# Sheet1.net
KiCad netlist of a schematic drawn in Altium Designer
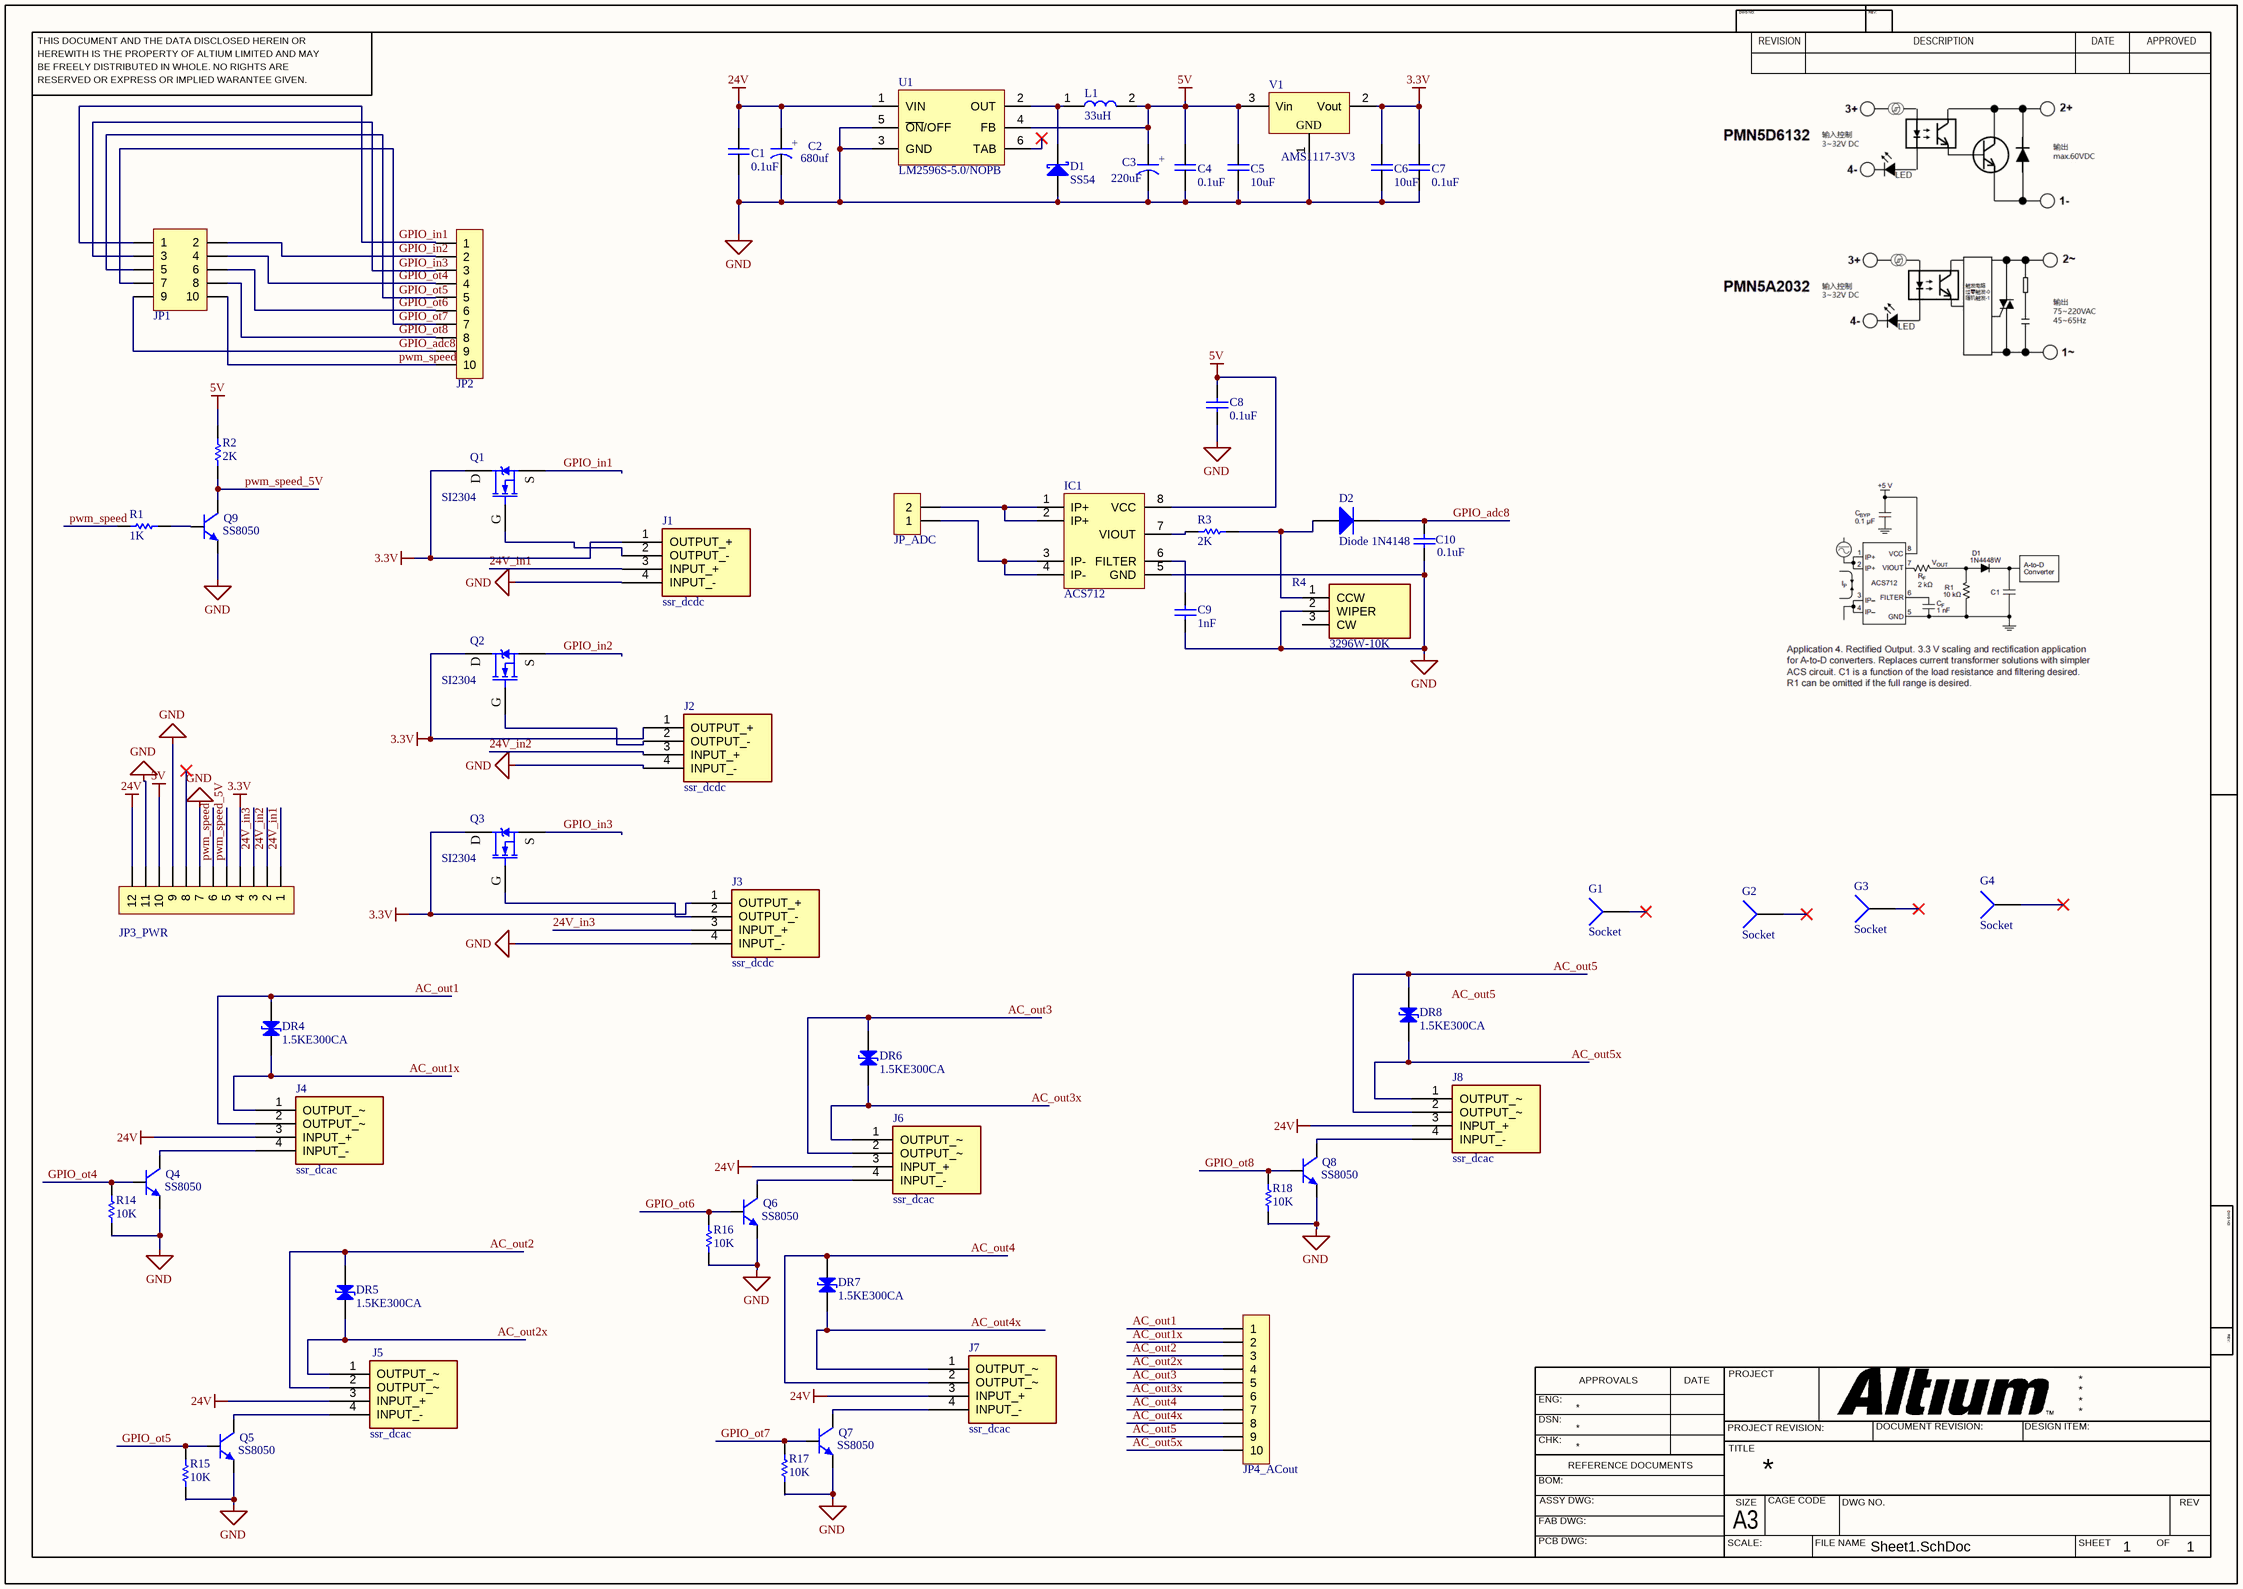
[diagram p0: Sheet1.SchDoc]

(export (version "E")
  (design (tool "Eeschema 10.0.6"))
  (components
    (comp (ref "C1") (value "0.1uF") (footprint "C 0805_M") (libsource (lib "LM2596S_5.0") (part "CAP-SMT")))
    (comp (ref "C2")
      (value "680uf")
      (footprint "CAP 5.0*12.5*20")
      (description "CAP-SMD")
      (libsource (lib "LM2596S_5.0") (part "CAP-SMD"))
    )
    (comp (ref "C3")
      (value "220uF")
      (footprint "CAP 5.0*10*16")
      (description "CAP-SMD")
      (libsource (lib "LM2596S_5.0") (part "CAP-SMD"))
    )
    (comp (ref "C4") (value "0.1uF") (footprint "C 0805_M") (libsource (lib "LM2596S_5.0") (part "CAP-SMT")))
    (comp (ref "C5") (value "10uF") (footprint "C 0805_M") (libsource (lib "LM2596S_5.0") (part "CAP-SMT")))
    (comp (ref "C6") (value "10uF") (footprint "C 0805_M") (libsource (lib "LM2596S_5.0") (part "CAP-SMT")))
    (comp (ref "C7") (value "0.1uF") (footprint "C 0805_M") (libsource (lib "LM2596S_5.0") (part "CAP-SMT")))
    (comp (ref "C8")
      (value "0.1uF")
      (footprint "C 0805_M")
      (description "Capacitor")
      (fields (field (name "PUBLISHER") "Altium Limited"))
      (libsource (lib "Miscellaneous Devices") (part "Cap"))
    )
    (comp (ref "C9")
      (value "1nF")
      (footprint "C 0805_M")
      (description "Capacitor")
      (fields (field (name "PUBLISHER") "Altium Limited"))
      (libsource (lib "Miscellaneous Devices") (part "Cap"))
    )
    (comp (ref "C10")
      (value "0.1uF")
      (footprint "C 0805_M")
      (description "Capacitor")
      (fields (field (name "PUBLISHER") "Altium Limited"))
      (libsource (lib "Miscellaneous Devices") (part "Cap"))
    )
    (comp (ref "D1") (value "SS54") (footprint "SMC") (libsource (lib "LM2596S_5.0") (part "DIO")))
    (comp (ref "D2")
      (value "Diode 1N4148")
      (footprint "SOD-123")
      (description "High Conductance Fast Diode")
      (fields (field (name "PUBLISHER") "Altium Limited"))
      (libsource (lib "Miscellaneous Devices") (part "Diode 1N4148"))
    )
    (comp (ref "DR4")
      (value "1.5KE300CA")
      (footprint "DO-15")
      (description "瞬态电压抑制二极管")
      (fields (field (name "版权归属") "源创客"))
      (libsource (lib "8.1   - 二极管-整流桥") (part "DR"))
    )
    (comp (ref "DR5")
      (value "1.5KE300CA")
      (footprint "DO-15")
      (description "瞬态电压抑制二极管")
      (fields (field (name "版权归属") "源创客"))
      (libsource (lib "8.1   - 二极管-整流桥") (part "DR"))
    )
    (comp (ref "DR6")
      (value "1.5KE300CA")
      (footprint "DO-15")
      (description "瞬态电压抑制二极管")
      (fields (field (name "版权归属") "源创客"))
      (libsource (lib "8.1   - 二极管-整流桥") (part "DR"))
    )
    (comp (ref "DR7")
      (value "1.5KE300CA")
      (footprint "DO-15")
      (description "瞬态电压抑制二极管")
      (fields (field (name "版权归属") "源创客"))
      (libsource (lib "8.1   - 二极管-整流桥") (part "DR"))
    )
    (comp (ref "DR8")
      (value "1.5KE300CA")
      (footprint "DO-15")
      (description "瞬态电压抑制二极管")
      (fields (field (name "版权归属") "源创客"))
      (libsource (lib "8.1   - 二极管-整流桥") (part "DR"))
    )
    (comp (ref "G1")
      (value "Socket")
      (footprint "M3x6_L")
      (fields (field (name "PUBLISHER") "Altium Limited"))
      (libsource (lib "Miscellaneous Connectors") (part "Socket"))
    )
    (comp (ref "G2")
      (value "Socket")
      (footprint "M3x6_L")
      (fields (field (name "PUBLISHER") "Altium Limited"))
      (libsource (lib "Miscellaneous Connectors") (part "Socket"))
    )
    (comp (ref "G3")
      (value "Socket")
      (footprint "M3x6_L")
      (fields (field (name "PUBLISHER") "Altium Limited"))
      (libsource (lib "Miscellaneous Connectors") (part "Socket"))
    )
    (comp (ref "G4")
      (value "Socket")
      (footprint "M3x6_L")
      (fields (field (name "PUBLISHER") "Altium Limited"))
      (libsource (lib "Miscellaneous Connectors") (part "Socket"))
    )
    (comp (ref "IC1")
      (value "ACS712")
      (footprint "SOP8_M")
      (description "电流检测芯片")
      (fields (field (name "版权归属") "源创客"))
      (libsource (lib "1.1   - IC芯片") (part "ACS712"))
    )
    (comp (ref "J1")
      (value "ssr_dcdc")
      (footprint "2982647")
      (description "Connector")
      (fields
        (field (name "MANUFACTURER_PART_NUMBER") "2982647")
        (field (name "MOUSER PART NUMBER") "651-2982647")
      )
      (libsource (lib "SamacSys") (part "ssr_dcdc"))
    )
    (comp (ref "J2")
      (value "ssr_dcdc")
      (footprint "2982647")
      (description "Connector")
      (fields
        (field (name "MANUFACTURER_PART_NUMBER") "2982647")
        (field (name "MOUSER PART NUMBER") "651-2982647")
      )
      (libsource (lib "SamacSys") (part "ssr_dcdc"))
    )
    (comp (ref "J3")
      (value "ssr_dcdc")
      (footprint "2982647")
      (description "Connector")
      (fields
        (field (name "MANUFACTURER_PART_NUMBER") "2982647")
        (field (name "MOUSER PART NUMBER") "651-2982647")
      )
      (libsource (lib "SamacSys") (part "ssr_dcdc"))
    )
    (comp (ref "J4")
      (value "ssr_dcac")
      (footprint "SSR_DCAC")
      (description "Connector")
      (fields
        (field (name "MANUFACTURER_PART_NUMBER") "2982647")
        (field (name "MOUSER PART NUMBER") "651-2982647")
      )
      (libsource (lib "SamacSys") (part "ssr_dcac"))
    )
    (comp (ref "J5")
      (value "ssr_dcac")
      (footprint "SSR_DCAC")
      (description "Connector")
      (fields
        (field (name "MANUFACTURER_PART_NUMBER") "2982647")
        (field (name "MOUSER PART NUMBER") "651-2982647")
      )
      (libsource (lib "SamacSys") (part "ssr_dcac"))
    )
    (comp (ref "J6")
      (value "ssr_dcac")
      (footprint "SSR_DCAC")
      (description "Connector")
      (fields
        (field (name "MANUFACTURER_PART_NUMBER") "2982647")
        (field (name "MOUSER PART NUMBER") "651-2982647")
      )
      (libsource (lib "SamacSys") (part "ssr_dcac"))
    )
    (comp (ref "J7")
      (value "ssr_dcac")
      (footprint "SSR_DCAC")
      (description "Connector")
      (fields
        (field (name "MANUFACTURER_PART_NUMBER") "2982647")
        (field (name "MOUSER PART NUMBER") "651-2982647")
      )
      (libsource (lib "SamacSys") (part "ssr_dcac"))
    )
    (comp (ref "J8")
      (value "ssr_dcac")
      (footprint "SSR_DCAC")
      (description "Connector")
      (fields
        (field (name "MANUFACTURER_PART_NUMBER") "2982647")
        (field (name "MOUSER PART NUMBER") "651-2982647")
      )
      (libsource (lib "SamacSys") (part "ssr_dcac"))
    )
    (comp (ref "JP1")
      (value "Header 5X2")
      (footprint "IDC2.54-LI-2x5P")
      (description "5*2P接插件")
      (fields (field (name "版权归属") "源创客"))
      (libsource (lib "4.5   - 接插件-脚距2.54") (part "Header 5X2"))
    )
    (comp (ref "JP2")
      (value "HDR-1X10")
      (footprint "KF128-3.81-10P")
      (description "10P接插件")
      (fields (field (name "版权归属") "源创客"))
      (libsource (lib "4.6   - 接插件-脚距3.5") (part "Header 10"))
    )
    (comp (ref "JP3_PWR")
      (value "HDR-1X12")
      (footprint "KF128-3.81-12P")
      (description "12P接插件")
      (fields (field (name "版权归属") "源创客"))
      (libsource (lib "4.7   - 接插件-脚距3.81") (part "Header 12"))
    )
    (comp (ref "JP4_ACout")
      (value "HDR-1X10")
      (footprint "KF128-3.81-10P")
      (description "10P接插件")
      (fields (field (name "版权归属") "源创客"))
      (libsource (lib "4.6   - 接插件-脚距3.5") (part "Header 10"))
    )
    (comp (ref "JP_ADC")
      (value "HDR-1X2")
      (footprint "KF128-3.81-2P")
      (description "2P接插件")
      (fields (field (name "版权归属") "源创客"))
      (libsource (lib "4.7   - 接插件-脚距3.81") (part "Header 2"))
    )
    (comp (ref "L1") (value "33uH") (footprint "CDRH74") (libsource (lib "LM2596S_5.0") (part "L-CDRH74")))
    (comp (ref "Q1")
      (value "SI2304")
      (footprint "SOT23-3M")
      (description "N沟道场效应管")
      (fields (field (name "版权归属") "源创客"))
      (libsource (lib "6.1   - 场效应管-可控硅") (part "SI2302"))
    )
    (comp (ref "Q2")
      (value "SI2304")
      (footprint "SOT23-3M")
      (description "N沟道场效应管")
      (fields (field (name "版权归属") "源创客"))
      (libsource (lib "6.1   - 场效应管-可控硅") (part "SI2302"))
    )
    (comp (ref "Q3")
      (value "SI2304")
      (footprint "SOT23-3M")
      (description "N沟道场效应管")
      (fields (field (name "版权归属") "源创客"))
      (libsource (lib "6.1   - 场效应管-可控硅") (part "SI2302"))
    )
    (comp (ref "Q4")
      (value "SS8050")
      (footprint "TO92A")
      (description "高频放大-NPN型")
      (fields (field (name "版权归属") "源创客"))
      (libsource (lib "6.2   - 三极管") (part "8050-DIP"))
    )
    (comp (ref "Q5")
      (value "SS8050")
      (footprint "TO92A")
      (description "高频放大-NPN型")
      (fields (field (name "版权归属") "源创客"))
      (libsource (lib "6.2   - 三极管") (part "8050-DIP"))
    )
    (comp (ref "Q6")
      (value "SS8050")
      (footprint "TO92A")
      (description "高频放大-NPN型")
      (fields (field (name "版权归属") "源创客"))
      (libsource (lib "6.2   - 三极管") (part "8050-DIP"))
    )
    (comp (ref "Q7")
      (value "SS8050")
      (footprint "TO92A")
      (description "高频放大-NPN型")
      (fields (field (name "版权归属") "源创客"))
      (libsource (lib "6.2   - 三极管") (part "8050-DIP"))
    )
    (comp (ref "Q8")
      (value "SS8050")
      (footprint "TO92A")
      (description "高频放大-NPN型")
      (fields (field (name "版权归属") "源创客"))
      (libsource (lib "6.2   - 三极管") (part "8050-DIP"))
    )
    (comp (ref "Q9")
      (value "SS8050")
      (footprint "TO92A")
      (description "高频放大-NPN型")
      (fields (field (name "版权归属") "源创客"))
      (libsource (lib "6.2   - 三极管") (part "8050-DIP"))
    )
    (comp (ref "R1")
      (value "1K")
      (footprint "R 0805_M")
      (description "Resistor")
      (fields (field (name "PUBLISHER") "Altium Limited"))
      (libsource (lib "Miscellaneous Devices") (part "Res1"))
    )
    (comp (ref "R2")
      (value "2K")
      (footprint "R 0805_M")
      (description "Resistor")
      (fields (field (name "PUBLISHER") "Altium Limited"))
      (libsource (lib "Miscellaneous Devices") (part "Res1"))
    )
    (comp (ref "R3")
      (value "2K")
      (footprint "R 0805_M")
      (description "Resistor")
      (fields (field (name "PUBLISHER") "Altium Limited"))
      (libsource (lib "Miscellaneous Devices") (part "Res1"))
    )
    (comp (ref "R4")
      (value "3296W-10K")
      (footprint "3296W")
      (description "Resistor")
      (fields
        (field (name "MANUFACTURER_PART_NUMBER") "3296W-1-100LF")
        (field (name "MOUSER PART NUMBER") "652-3296W-1-100LF")
      )
      (libsource (lib "*") (part "3296W-1-100LF"))
    )
    (comp (ref "R14")
      (value "10K")
      (footprint "R 0805_M")
      (description "Resistor")
      (fields (field (name "PUBLISHER") "Altium Limited"))
      (libsource (lib "Miscellaneous Devices") (part "Res1"))
    )
    (comp (ref "R15")
      (value "10K")
      (footprint "R 0805_M")
      (description "Resistor")
      (fields (field (name "PUBLISHER") "Altium Limited"))
      (libsource (lib "Miscellaneous Devices") (part "Res1"))
    )
    (comp (ref "R16")
      (value "10K")
      (footprint "R 0805_M")
      (description "Resistor")
      (fields (field (name "PUBLISHER") "Altium Limited"))
      (libsource (lib "Miscellaneous Devices") (part "Res1"))
    )
    (comp (ref "R17")
      (value "10K")
      (footprint "R 0805_M")
      (description "Resistor")
      (fields (field (name "PUBLISHER") "Altium Limited"))
      (libsource (lib "Miscellaneous Devices") (part "Res1"))
    )
    (comp (ref "R18")
      (value "10K")
      (footprint "R 0805_M")
      (description "Resistor")
      (fields (field (name "PUBLISHER") "Altium Limited"))
      (libsource (lib "Miscellaneous Devices") (part "Res1"))
    )
    (comp (ref "U1")
      (value "LM2596S-5.0/NOPB")
      (footprint "TO263-5A")
      (description "SIMPLE SWITCHER® Power Converter 150 KHz 3A Step-Down Voltage Regulator, 5-pin TO-263, Pb-Free")
      (fields (field (name "MANUFACTURER") "Texas Instruments"))
      (libsource (lib "LM2596S_5.0") (part "LM2596S-5.0"))
    )
    (comp (ref "V1")
      (value "AMS1117-3V3")
      (footprint "SOT223_M")
      (description "三端稳压芯片")
      (fields (field (name "版权归属") "源创客"))
      (libsource (lib "1.3   - 电源类芯片") (part "AMS1117"))
    )
  )
  (nets
    (net (code "1") (name "/24V_in1") (class "Default")
      (node (ref "J1") (pin "3") (pinfunction "INPUT_+_3") (pintype "passive"))
      (node (ref "JP3_PWR") (pin "1") (pinfunction "1_1") (pintype "passive"))
    )
    (net (code "2") (name "/24V_in2") (class "Default")
      (node (ref "J2") (pin "3") (pinfunction "INPUT_+_3") (pintype "passive"))
      (node (ref "JP3_PWR") (pin "2") (pinfunction "2_2") (pintype "passive"))
    )
    (net (code "3") (name "/24V_in3") (class "Default")
      (node (ref "J3") (pin "3") (pinfunction "INPUT_+_3") (pintype "passive"))
      (node (ref "JP3_PWR") (pin "3") (pinfunction "3_3") (pintype "passive"))
    )
    (net (code "4") (name "/AC_out1") (class "Default")
      (node (ref "DR4") (pin "1") (pinfunction "A_1") (pintype "passive"))
      (node (ref "J4") (pin "2") (pinfunction "OUTPUT_~_2") (pintype "passive"))
      (node (ref "JP4_ACout") (pin "1") (pinfunction "1_1") (pintype "passive"))
    )
    (net (code "5") (name "/AC_out1x") (class "Default")
      (node (ref "DR4") (pin "2") (pinfunction "K_2") (pintype "passive"))
      (node (ref "J4") (pin "1") (pinfunction "OUTPUT_~_1") (pintype "passive"))
      (node (ref "JP4_ACout") (pin "2") (pinfunction "2_2") (pintype "passive"))
    )
    (net (code "6") (name "/AC_out2") (class "Default")
      (node (ref "DR5") (pin "1") (pinfunction "A_1") (pintype "passive"))
      (node (ref "J5") (pin "2") (pinfunction "OUTPUT_~_2") (pintype "passive"))
      (node (ref "JP4_ACout") (pin "3") (pinfunction "3_3") (pintype "passive"))
    )
    (net (code "7") (name "/AC_out2x") (class "Default")
      (node (ref "DR5") (pin "2") (pinfunction "K_2") (pintype "passive"))
      (node (ref "J5") (pin "1") (pinfunction "OUTPUT_~_1") (pintype "passive"))
      (node (ref "JP4_ACout") (pin "4") (pinfunction "4_4") (pintype "passive"))
    )
    (net (code "8") (name "/AC_out3") (class "Default")
      (node (ref "DR6") (pin "1") (pinfunction "A_1") (pintype "passive"))
      (node (ref "J6") (pin "2") (pinfunction "OUTPUT_~_2") (pintype "passive"))
      (node (ref "JP4_ACout") (pin "5") (pinfunction "5_5") (pintype "passive"))
    )
    (net (code "9") (name "/AC_out3x") (class "Default")
      (node (ref "DR6") (pin "2") (pinfunction "K_2") (pintype "passive"))
      (node (ref "J6") (pin "1") (pinfunction "OUTPUT_~_1") (pintype "passive"))
      (node (ref "JP4_ACout") (pin "6") (pinfunction "6_6") (pintype "passive"))
    )
    (net (code "10") (name "/AC_out4") (class "Default")
      (node (ref "DR7") (pin "1") (pinfunction "A_1") (pintype "passive"))
      (node (ref "J7") (pin "2") (pinfunction "OUTPUT_~_2") (pintype "passive"))
      (node (ref "JP4_ACout") (pin "7") (pinfunction "7_7") (pintype "passive"))
    )
    (net (code "11") (name "/AC_out4x") (class "Default")
      (node (ref "DR7") (pin "2") (pinfunction "K_2") (pintype "passive"))
      (node (ref "J7") (pin "1") (pinfunction "OUTPUT_~_1") (pintype "passive"))
      (node (ref "JP4_ACout") (pin "8") (pinfunction "8_8") (pintype "passive"))
    )
    (net (code "12") (name "/AC_out5") (class "Default")
      (node (ref "DR8") (pin "1") (pinfunction "A_1") (pintype "passive"))
      (node (ref "J8") (pin "2") (pinfunction "OUTPUT_~_2") (pintype "passive"))
      (node (ref "JP4_ACout") (pin "9") (pinfunction "9_9") (pintype "passive"))
    )
    (net (code "13") (name "/AC_out5x") (class "Default")
      (node (ref "DR8") (pin "2") (pinfunction "K_2") (pintype "passive"))
      (node (ref "J8") (pin "1") (pinfunction "OUTPUT_~_1") (pintype "passive"))
      (node (ref "JP4_ACout") (pin "10") (pinfunction "10_10") (pintype "passive"))
    )
    (net (code "14") (name "/GPIO_adc8") (class "Default")
      (node (ref "C10") (pin "2") (pinfunction "2_2") (pintype "passive"))
      (node (ref "D2") (pin "2") (pinfunction "K_2") (pintype "passive"))
      (node (ref "JP1") (pin "9") (pinfunction "9_9") (pintype "passive"))
      (node (ref "JP2") (pin "9") (pinfunction "9_9") (pintype "passive"))
    )
    (net (code "15") (name "/GPIO_in1") (class "Default")
      (node (ref "JP1") (pin "1") (pinfunction "1_1") (pintype "passive"))
      (node (ref "JP2") (pin "1") (pinfunction "1_1") (pintype "passive"))
      (node (ref "Q1") (pin "2") (pinfunction "S_2") (pintype "passive"))
    )
    (net (code "16") (name "/GPIO_in2") (class "Default")
      (node (ref "JP1") (pin "2") (pinfunction "2_2") (pintype "passive"))
      (node (ref "JP2") (pin "2") (pinfunction "2_2") (pintype "passive"))
      (node (ref "Q2") (pin "2") (pinfunction "S_2") (pintype "passive"))
    )
    (net (code "17") (name "/GPIO_in3") (class "Default")
      (node (ref "JP1") (pin "3") (pinfunction "3_3") (pintype "passive"))
      (node (ref "JP2") (pin "3") (pinfunction "3_3") (pintype "passive"))
      (node (ref "Q3") (pin "2") (pinfunction "S_2") (pintype "passive"))
    )
    (net (code "18") (name "/GPIO_ot4") (class "Default")
      (node (ref "JP1") (pin "4") (pinfunction "4_4") (pintype "passive"))
      (node (ref "JP2") (pin "4") (pinfunction "4_4") (pintype "passive"))
      (node (ref "Q4") (pin "2") (pinfunction "B_2") (pintype "passive"))
      (node (ref "R14") (pin "1") (pinfunction "1_1") (pintype "passive"))
    )
    (net (code "19") (name "/GPIO_ot5") (class "Default")
      (node (ref "JP1") (pin "5") (pinfunction "5_5") (pintype "passive"))
      (node (ref "JP2") (pin "5") (pinfunction "5_5") (pintype "passive"))
      (node (ref "Q5") (pin "2") (pinfunction "B_2") (pintype "passive"))
      (node (ref "R15") (pin "1") (pinfunction "1_1") (pintype "passive"))
    )
    (net (code "20") (name "/GPIO_ot6") (class "Default")
      (node (ref "JP1") (pin "6") (pinfunction "6_6") (pintype "passive"))
      (node (ref "JP2") (pin "6") (pinfunction "6_6") (pintype "passive"))
      (node (ref "Q6") (pin "2") (pinfunction "B_2") (pintype "passive"))
      (node (ref "R16") (pin "1") (pinfunction "1_1") (pintype "passive"))
    )
    (net (code "21") (name "/GPIO_ot7") (class "Default")
      (node (ref "JP1") (pin "7") (pinfunction "7_7") (pintype "passive"))
      (node (ref "JP2") (pin "7") (pinfunction "7_7") (pintype "passive"))
      (node (ref "Q7") (pin "2") (pinfunction "B_2") (pintype "passive"))
      (node (ref "R17") (pin "1") (pinfunction "1_1") (pintype "passive"))
    )
    (net (code "22") (name "/GPIO_ot8") (class "Default")
      (node (ref "JP1") (pin "8") (pinfunction "8_8") (pintype "passive"))
      (node (ref "JP2") (pin "8") (pinfunction "8_8") (pintype "passive"))
      (node (ref "Q8") (pin "2") (pinfunction "B_2") (pintype "passive"))
      (node (ref "R18") (pin "1") (pinfunction "1_1") (pintype "passive"))
    )
    (net (code "23") (name "/pwm_speed") (class "Default")
      (node (ref "JP1") (pin "10") (pinfunction "10_10") (pintype "passive"))
      (node (ref "JP2") (pin "10") (pinfunction "10_10") (pintype "passive"))
      (node (ref "JP3_PWR") (pin "6") (pinfunction "6_6") (pintype "passive"))
      (node (ref "R1") (pin "1") (pinfunction "1_1") (pintype "passive"))
    )
    (net (code "24") (name "/pwm_speed_5V") (class "Default")
      (node (ref "JP3_PWR") (pin "5") (pinfunction "5_5") (pintype "passive"))
      (node (ref "Q9") (pin "3") (pinfunction "C_3") (pintype "passive"))
      (node (ref "R2") (pin "1") (pinfunction "1_1") (pintype "passive"))
    )
    (net (code "25") (name "3.3V") (class "Default")
      (node (ref "C6") (pin "2") (pinfunction "2_2") (pintype "passive"))
      (node (ref "C7") (pin "2") (pinfunction "2_2") (pintype "passive"))
      (node (ref "J1") (pin "1") (pinfunction "OUTPUT_+_1") (pintype "passive"))
      (node (ref "J2") (pin "1") (pinfunction "OUTPUT_+_1") (pintype "passive"))
      (node (ref "J3") (pin "1") (pinfunction "OUTPUT_+_1") (pintype "passive"))
      (node (ref "JP3_PWR") (pin "4") (pinfunction "4_4") (pintype "passive"))
      (node (ref "Q1") (pin "3") (pinfunction "D_3") (pintype "passive"))
      (node (ref "Q2") (pin "3") (pinfunction "D_3") (pintype "passive"))
      (node (ref "Q3") (pin "3") (pinfunction "D_3") (pintype "passive"))
      (node (ref "V1") (pin "2") (pinfunction "Vout_2") (pintype "passive"))
    )
    (net (code "26") (name "5V") (class "Default")
      (node (ref "C3") (pin "2") (pinfunction "2_2") (pintype "passive"))
      (node (ref "C4") (pin "2") (pinfunction "2_2") (pintype "passive"))
      (node (ref "C5") (pin "2") (pinfunction "2_2") (pintype "passive"))
      (node (ref "C8") (pin "2") (pinfunction "2_2") (pintype "passive"))
      (node (ref "IC1") (pin "8") (pinfunction "VCC_8") (pintype "passive"))
      (node (ref "JP3_PWR") (pin "10") (pinfunction "10_10") (pintype "passive"))
      (node (ref "L1") (pin "2") (pinfunction "2_2") (pintype "passive"))
      (node (ref "R2") (pin "2") (pinfunction "2_2") (pintype "passive"))
      (node (ref "U1") (pin "4") (pinfunction "FB_4") (pintype "passive"))
      (node (ref "V1") (pin "3") (pinfunction "Vin_3") (pintype "passive"))
    )
    (net (code "27") (name "24V") (class "Default")
      (node (ref "C1") (pin "2") (pinfunction "2_2") (pintype "passive"))
      (node (ref "C2") (pin "2") (pinfunction "2_2") (pintype "passive"))
      (node (ref "J4") (pin "3") (pinfunction "INPUT_+_3") (pintype "passive"))
      (node (ref "J5") (pin "3") (pinfunction "INPUT_+_3") (pintype "passive"))
      (node (ref "J6") (pin "3") (pinfunction "INPUT_+_3") (pintype "passive"))
      (node (ref "J7") (pin "3") (pinfunction "INPUT_+_3") (pintype "passive"))
      (node (ref "J8") (pin "3") (pinfunction "INPUT_+_3") (pintype "passive"))
      (node (ref "JP3_PWR") (pin "12") (pinfunction "12_12") (pintype "passive"))
      (node (ref "U1") (pin "1") (pinfunction "VIN_1") (pintype "power_in"))
    )
    (net (code "28") (name "GND") (class "Default")
      (node (ref "C1") (pin "1") (pinfunction "1_1") (pintype "passive"))
      (node (ref "C10") (pin "1") (pinfunction "1_1") (pintype "passive"))
      (node (ref "C2") (pin "1") (pinfunction "1_1") (pintype "passive"))
      (node (ref "C3") (pin "1") (pinfunction "1_1") (pintype "passive"))
      (node (ref "C4") (pin "1") (pinfunction "1_1") (pintype "passive"))
      (node (ref "C5") (pin "1") (pinfunction "1_1") (pintype "passive"))
      (node (ref "C6") (pin "1") (pinfunction "1_1") (pintype "passive"))
      (node (ref "C7") (pin "1") (pinfunction "1_1") (pintype "passive"))
      (node (ref "C8") (pin "1") (pinfunction "1_1") (pintype "passive"))
      (node (ref "C9") (pin "1") (pinfunction "1_1") (pintype "passive"))
      (node (ref "D1") (pin "1") (pinfunction "1_1") (pintype "passive"))
      (node (ref "IC1") (pin "5") (pinfunction "GND_5") (pintype "passive"))
      (node (ref "J1") (pin "4") (pinfunction "INPUT_-_4") (pintype "passive"))
      (node (ref "J2") (pin "4") (pinfunction "INPUT_-_4") (pintype "passive"))
      (node (ref "J3") (pin "4") (pinfunction "INPUT_-_4") (pintype "passive"))
      (node (ref "JP3_PWR") (pin "11") (pinfunction "11_11") (pintype "passive"))
      (node (ref "JP3_PWR") (pin "7") (pinfunction "7_7") (pintype "passive"))
      (node (ref "JP3_PWR") (pin "9") (pinfunction "9_9") (pintype "passive"))
      (node (ref "Q4") (pin "1") (pinfunction "E_1") (pintype "passive"))
      (node (ref "Q5") (pin "1") (pinfunction "E_1") (pintype "passive"))
      (node (ref "Q6") (pin "1") (pinfunction "E_1") (pintype "passive"))
      (node (ref "Q7") (pin "1") (pinfunction "E_1") (pintype "passive"))
      (node (ref "Q8") (pin "1") (pinfunction "E_1") (pintype "passive"))
      (node (ref "Q9") (pin "1") (pinfunction "E_1") (pintype "passive"))
      (node (ref "R14") (pin "2") (pinfunction "2_2") (pintype "passive"))
      (node (ref "R15") (pin "2") (pinfunction "2_2") (pintype "passive"))
      (node (ref "R16") (pin "2") (pinfunction "2_2") (pintype "passive"))
      (node (ref "R17") (pin "2") (pinfunction "2_2") (pintype "passive"))
      (node (ref "R18") (pin "2") (pinfunction "2_2") (pintype "passive"))
      (node (ref "R4") (pin "2") (pinfunction "WIPER_2") (pintype "passive"))
      (node (ref "U1") (pin "3") (pinfunction "GND_3") (pintype "power_in"))
      (node (ref "U1") (pin "5") (pinfunction "~{ON}/OFF_5") (pintype "passive"))
      (node (ref "V1") (pin "1") (pinfunction "GND_1") (pintype "passive"))
    )
    (net (code "29") (name "Net-(D2-A)") (class "Default")
      (node (ref "D2") (pin "1") (pinfunction "A_1") (pintype "passive"))
      (node (ref "R3") (pin "2") (pinfunction "2_2") (pintype "passive"))
      (node (ref "R4") (pin "1") (pinfunction "CCW_1") (pintype "passive"))
    )
    (net (code "30") (name "Net-(IC1-FILTER)") (class "Default")
      (node (ref "C9") (pin "2") (pinfunction "2_2") (pintype "passive"))
      (node (ref "IC1") (pin "6") (pinfunction "FILTER_6") (pintype "passive"))
    )
    (net (code "31") (name "Net-(IC1-IP+-Pad1)") (class "Default")
      (node (ref "IC1") (pin "1") (pinfunction "IP+_1") (pintype "passive"))
      (node (ref "IC1") (pin "2") (pinfunction "IP+_2") (pintype "passive"))
      (node (ref "JP_ADC") (pin "2") (pinfunction "2_2") (pintype "passive"))
    )
    (net (code "32") (name "Net-(IC1-IP--Pad3)") (class "Default")
      (node (ref "IC1") (pin "3") (pinfunction "IP-_3") (pintype "passive"))
      (node (ref "IC1") (pin "4") (pinfunction "IP-_4") (pintype "passive"))
      (node (ref "JP_ADC") (pin "1") (pinfunction "1_1") (pintype "passive"))
    )
    (net (code "33") (name "Net-(IC1-VIOUT)") (class "Default")
      (node (ref "IC1") (pin "7") (pinfunction "VIOUT_7") (pintype "passive"))
      (node (ref "R3") (pin "1") (pinfunction "1_1") (pintype "passive"))
    )
    (net (code "34") (name "Net-(J1-OUTPUT_-)") (class "Default")
      (node (ref "J1") (pin "2") (pinfunction "OUTPUT_-_2") (pintype "passive"))
      (node (ref "Q1") (pin "1") (pinfunction "G_1") (pintype "passive"))
    )
    (net (code "35") (name "Net-(J2-OUTPUT_-)") (class "Default")
      (node (ref "J2") (pin "2") (pinfunction "OUTPUT_-_2") (pintype "passive"))
      (node (ref "Q2") (pin "1") (pinfunction "G_1") (pintype "passive"))
    )
    (net (code "36") (name "Net-(J3-OUTPUT_-)") (class "Default")
      (node (ref "J3") (pin "2") (pinfunction "OUTPUT_-_2") (pintype "passive"))
      (node (ref "Q3") (pin "1") (pinfunction "G_1") (pintype "passive"))
    )
    (net (code "37") (name "Net-(J4-INPUT_-)") (class "Default")
      (node (ref "J4") (pin "4") (pinfunction "INPUT_-_4") (pintype "passive"))
      (node (ref "Q4") (pin "3") (pinfunction "C_3") (pintype "passive"))
    )
    (net (code "38") (name "Net-(J5-INPUT_-)") (class "Default")
      (node (ref "J5") (pin "4") (pinfunction "INPUT_-_4") (pintype "passive"))
      (node (ref "Q5") (pin "3") (pinfunction "C_3") (pintype "passive"))
    )
    (net (code "39") (name "Net-(J6-INPUT_-)") (class "Default")
      (node (ref "J6") (pin "4") (pinfunction "INPUT_-_4") (pintype "passive"))
      (node (ref "Q6") (pin "3") (pinfunction "C_3") (pintype "passive"))
    )
    (net (code "40") (name "Net-(J7-INPUT_-)") (class "Default")
      (node (ref "J7") (pin "4") (pinfunction "INPUT_-_4") (pintype "passive"))
      (node (ref "Q7") (pin "3") (pinfunction "C_3") (pintype "passive"))
    )
    (net (code "41") (name "Net-(J8-INPUT_-)") (class "Default")
      (node (ref "J8") (pin "4") (pinfunction "INPUT_-_4") (pintype "passive"))
      (node (ref "Q8") (pin "3") (pinfunction "C_3") (pintype "passive"))
    )
    (net (code "42") (name "Net-(Q9-B)") (class "Default")
      (node (ref "Q9") (pin "2") (pinfunction "B_2") (pintype "passive"))
      (node (ref "R1") (pin "2") (pinfunction "2_2") (pintype "passive"))
    )
    (net (code "43") (name "Net-(U1-OUT)") (class "Default")
      (node (ref "D1") (pin "2") (pinfunction "2_2") (pintype "passive"))
      (node (ref "L1") (pin "1") (pinfunction "1_1") (pintype "passive"))
      (node (ref "U1") (pin "2") (pinfunction "OUT_2") (pintype "power_in"))
    )
    (net (code "44") (name "unconnected-(G1-Pad1)") (class "Default")
      (node (ref "G1") (pin "1") (pinfunction "1_1") (pintype "passive+no_connect"))
    )
    (net (code "45") (name "unconnected-(G2-Pad1)") (class "Default")
      (node (ref "G2") (pin "1") (pinfunction "1_1") (pintype "passive+no_connect"))
    )
    (net (code "46") (name "unconnected-(G3-Pad1)") (class "Default")
      (node (ref "G3") (pin "1") (pinfunction "1_1") (pintype "passive+no_connect"))
    )
    (net (code "47") (name "unconnected-(G4-Pad1)") (class "Default")
      (node (ref "G4") (pin "1") (pinfunction "1_1") (pintype "passive+no_connect"))
    )
    (net (code "48") (name "unconnected-(JP3_PWR-Pad8)") (class "Default")
      (node (ref "JP3_PWR") (pin "8") (pinfunction "8_8") (pintype "passive+no_connect"))
    )
    (net (code "49") (name "unconnected-(R4-CW-Pad3)") (class "Default")
      (node (ref "R4") (pin "3") (pinfunction "CW_3") (pintype "passive"))
    )
    (net (code "50") (name "unconnected-(U1-TAB-Pad6)") (class "Default")
      (node (ref "U1") (pin "6") (pinfunction "TAB_6") (pintype "power_in+no_connect"))
    )
  )
)
